# TEC_Laser.net
KiCad netlist of a schematic drawn in Altium Designer
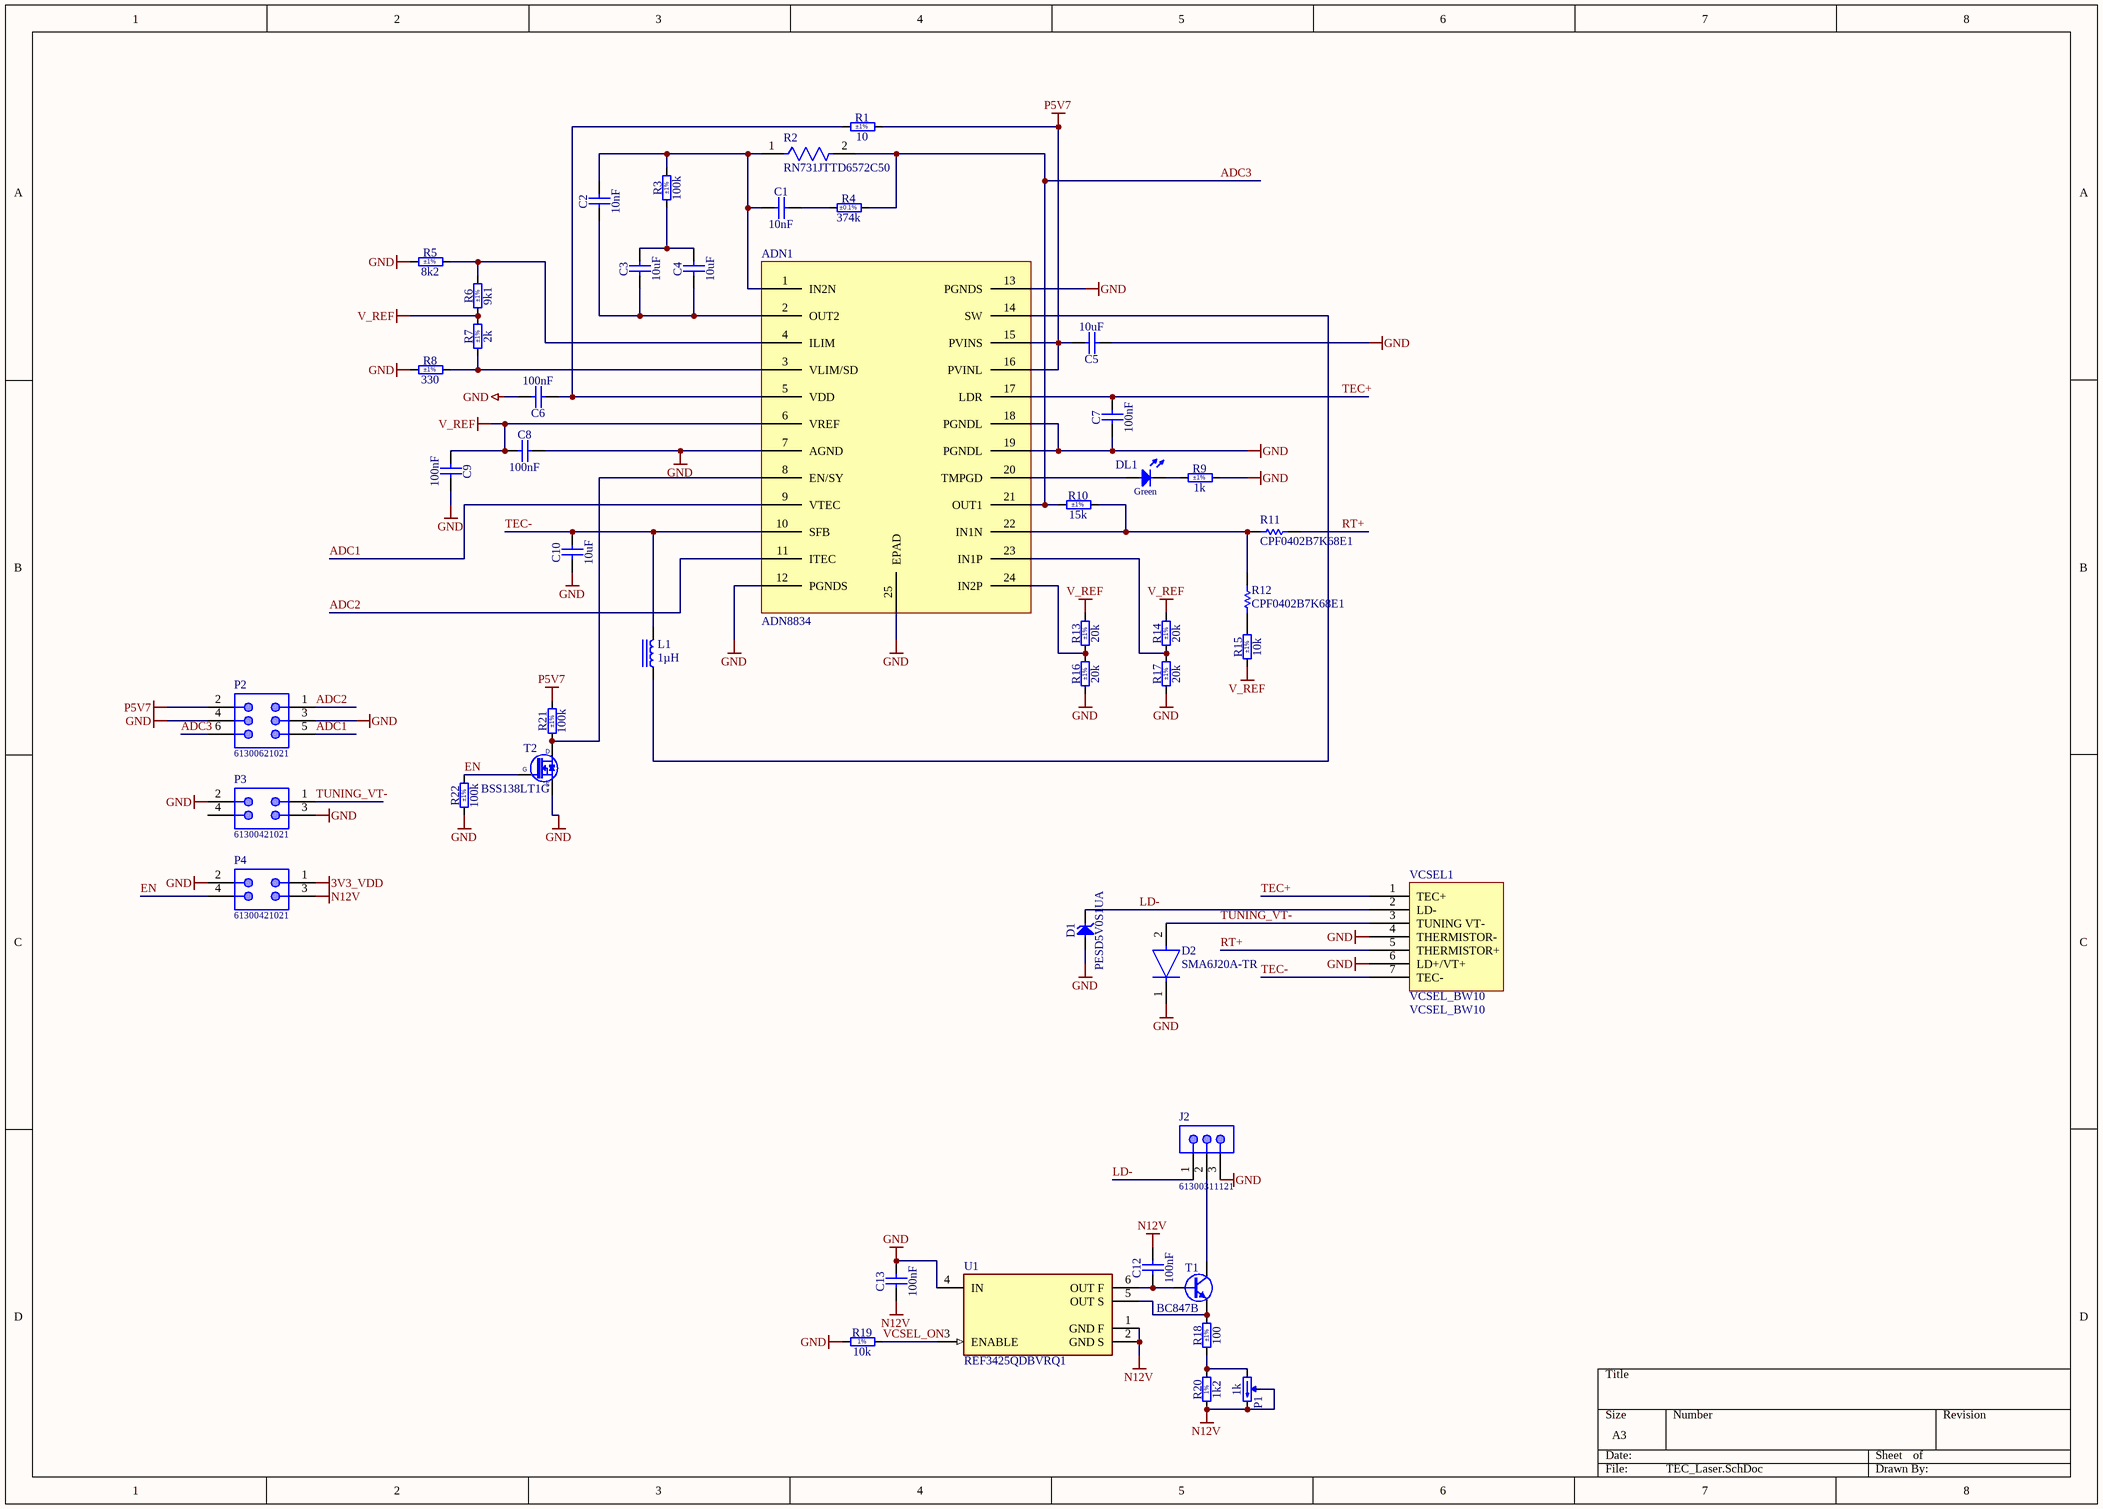
[diagram p0: TEC_Laser.SchDoc]

(export (version "E")
  (design (tool "Eeschema 10.0.6"))
  (components
    (comp (ref "ADN1")
      (value "ADN8834")
      (footprint "SMSC QFN-24 4x4MM")
      (description "TEC")
      (libsource (lib "VCSEL_Driver_Lib") (part "ADN8834"))
    )
    (comp (ref "C1")
      (value "10nF")
      (footprint "CAPC1005X55N")
      (description "Non-polarised capacitor")
      (fields
        (field (name "PART NUMBER") "CC0402_10NF_16V_10%_X7R")
        (field (name "VOLTAGE") "16V")
        (field (name "AUTHOR") "CERN DEM JLC")
      )
      (libsource (lib "Capacitors") (part "Capacitor - non polarized"))
    )
    (comp (ref "C2")
      (value "10nF")
      (footprint "CAPC1005X55N")
      (description "Non-polarised capacitor")
      (fields
        (field (name "PART NUMBER") "CC0402_10NF_16V_10%_X7R")
        (field (name "VOLTAGE") "16V")
        (field (name "AUTHOR") "CERN DEM JLC")
      )
      (libsource (lib "Capacitors") (part "Capacitor - non polarized"))
    )
    (comp (ref "C3")
      (value "10uF")
      (footprint "CAPC1608X80N")
      (description "Non-polarised capacitor")
      (fields
        (field (name "PART NUMBER") "CC0603_10UF_16V_20%_X5R")
        (field (name "VOLTAGE") "16V")
        (field (name "AUTHOR") "CERN DEM MR")
      )
      (libsource (lib "Capacitors") (part "Capacitor - non polarized"))
    )
    (comp (ref "C4")
      (value "10uF")
      (footprint "CAPC1608X80N")
      (description "Non-polarised capacitor")
      (fields
        (field (name "PART NUMBER") "CC0603_10UF_16V_20%_X5R")
        (field (name "VOLTAGE") "16V")
        (field (name "AUTHOR") "CERN DEM MR")
      )
      (libsource (lib "Capacitors") (part "Capacitor - non polarized"))
    )
    (comp (ref "C5")
      (value "10uF")
      (footprint "CAPC1005X70N")
      (description "Non-polarised capacitor")
      (fields
        (field (name "PART NUMBER") "CC0402_10UF_6.3V_20%_X5R")
        (field (name "VOLTAGE") "6.3V")
        (field (name "AUTHOR") "CERN DEM JLC")
      )
      (libsource (lib "Capacitors") (part "Capacitor - non polarized"))
    )
    (comp (ref "C6")
      (value "100nF")
      (footprint "CAPC1005X55N")
      (description "Non-polarised capacitor")
      (fields
        (field (name "PART NUMBER") "CC0402_100NF_16V_10%_X7R")
        (field (name "VOLTAGE") "16V")
        (field (name "AUTHOR") "CERN DEM JLC")
      )
      (libsource (lib "Capacitors") (part "Capacitor - non polarized"))
    )
    (comp (ref "C7")
      (value "100nF")
      (footprint "CAPC1005X55N")
      (description "Non-polarised capacitor")
      (fields
        (field (name "PART NUMBER") "CC0402_100NF_16V_10%_X7R")
        (field (name "VOLTAGE") "16V")
        (field (name "AUTHOR") "CERN DEM JLC")
      )
      (libsource (lib "Capacitors") (part "Capacitor - non polarized"))
    )
    (comp (ref "C8")
      (value "100nF")
      (footprint "CAPC1005X55N")
      (description "Non-polarised capacitor")
      (fields
        (field (name "PART NUMBER") "CC0402_100NF_16V_10%_X7R")
        (field (name "VOLTAGE") "16V")
        (field (name "AUTHOR") "CERN DEM JLC")
      )
      (libsource (lib "Capacitors") (part "Capacitor - non polarized"))
    )
    (comp (ref "C9")
      (value "100nF")
      (footprint "CAPC1005X55N")
      (description "Non-polarised capacitor")
      (fields
        (field (name "PART NUMBER") "CC0402_100NF_16V_10%_X7R")
        (field (name "VOLTAGE") "16V")
        (field (name "AUTHOR") "CERN DEM JLC")
      )
      (libsource (lib "Capacitors") (part "Capacitor - non polarized"))
    )
    (comp (ref "C10")
      (value "10uF")
      (footprint "CAPC1005X70N")
      (description "Non-polarised capacitor")
      (fields
        (field (name "PART NUMBER") "CC0402_10UF_6.3V_20%_X5R")
        (field (name "VOLTAGE") "6.3V")
        (field (name "AUTHOR") "CERN DEM JLC")
      )
      (libsource (lib "Capacitors") (part "Capacitor - non polarized"))
    )
    (comp (ref "C12")
      (value "100nF")
      (footprint "CAPC1005X55N")
      (description "Non-polarised capacitor")
      (fields
        (field (name "PART NUMBER") "CC0402_100NF_16V_10%_X7R")
        (field (name "VOLTAGE") "16V")
        (field (name "AUTHOR") "CERN DEM JLC")
      )
      (libsource (lib "Capacitors") (part "Capacitor - non polarized"))
    )
    (comp (ref "C13")
      (value "100nF")
      (footprint "CAPC1005X55N")
      (description "Non-polarised capacitor")
      (fields
        (field (name "PART NUMBER") "CC0402_100NF_16V_10%_X7R")
        (field (name "VOLTAGE") "16V")
        (field (name "AUTHOR") "CERN DEM JLC")
      )
      (libsource (lib "Capacitors") (part "Capacitor - non polarized"))
    )
    (comp (ref "D1")
      (value "PESD5V0S1UA")
      (footprint "SOD2512X110N")
      (description "Transient Voltage Suppressor Diode (Uni-Directional)")
      (fields
        (field (name "VOLTAGE") "5V")
        (field (name "POWER") "890W")
        (field (name "AUTHOR") "CERN DEM JLC")
      )
      (libsource (lib "ICs And Semiconductors") (part "Diode TVS Uni-Directional"))
    )
    (comp (ref "D2")
      (value "SMA6J20A-TR")
      (footprint "FP-SMA-MFG")
      (description "TVS DIODE 20V 36.8V SMA")
      (libsource (lib "Altium Content Vault") (part "d7152d700b627762746794eb795d46e"))
    )
    (comp (ref "DL1")
      (value "Green")
      (footprint "LED_OSRAM_LGL29K")
      (description "LED Green 1C 2A")
      (fields
        (field (name "PART NUMBER") "LED_OSRAM_LG L29K-G2J1-24-Z")
        (field (name "MANUFACTURER") "OSRAM")
        (field (name "AUTHOR") "CERN DEM JLC")
      )
      (libsource (lib "ICs And Semiconductors") (part "LED Green 1C 2A"))
    )
    (comp (ref "J2")
      (value "61300311121")
      (footprint "61300311121")
      (description "WR-PHD Pin Header, THT, pitch 2.54mm, Single Row, Vertical, 3pin")
      (fields (field (name "PUBLISHER") "Wurth Elektronik"))
      (libsource (lib "ALTIUM-WR-PHD_PIN_HEADER_SOCKET_HEADER-rev19a") (part "61300311121"))
    )
    (comp (ref "L1")
      (value "1µH")
      (footprint "IND 0806_2016")
      (description "FIXED IND 1UH 1.7A 107MOHM SMD")
      (fields
        (field (name "PART NUMBER") "SDED20161T-1R0MS")
        (field (name "MANUFACTURER") "Delta Electronics/Cyntec")
      )
      (libsource (lib "Celestial Altium Library - altium_library") (part "Inductor"))
    )
    (comp (ref "P1")
      (value "1k")
      (footprint "TRIM_VISHAY_T63XB")
      (description "Trimming Potentiometer")
      (fields
        (field (name "PART NUMBER") "TRIM_14T_1K_VISHAY_T63XB102KT20")
        (field (name "POWER") "0.25W")
        (field (name "AUTHOR") "CERN DEM JLC")
      )
      (libsource (lib "Resistors") (part "Trimming Potentiometer"))
    )
    (comp (ref "P2")
      (value "61300621021")
      (footprint "61300621021")
      (description "WR-PHD Pin Header, THT, pitch 2.54mm, Dual Row, Angled, 6p")
      (fields (field (name "MANUFACTURER") "Wurth Elektronik"))
      (libsource (lib "Altium_WR-PHD (rev20a)") (part "61300621021"))
    )
    (comp (ref "P3")
      (value "61300421021")
      (footprint "61300421021")
      (description "WR-PHD Pin Header, THT, pitch 2.54mm, Dual Row, Angled, 4p")
      (fields (field (name "MANUFACTURER") "Wurth Elektronik"))
      (libsource (lib "Altium_WR-PHD (rev20a)") (part "61300421021"))
    )
    (comp (ref "P4")
      (value "61300421021")
      (footprint "61300421021")
      (description "WR-PHD Pin Header, THT, pitch 2.54mm, Dual Row, Angled, 4p")
      (fields (field (name "MANUFACTURER") "Wurth Elektronik"))
      (libsource (lib "Altium_WR-PHD (rev20a)") (part "61300421021"))
    )
    (comp (ref "R1")
      (value "10")
      (footprint "RESC1005X40N")
      (description "Resistor - 1%")
      (fields
        (field (name "TOLERANCE") "±1%")
        (field (name "PART NUMBER") "R0402_10R_1%_0.0625W_200PPM")
        (field (name "POWER") "0.0625W")
        (field (name "AUTHOR") "CERN DEM JLC")
      )
      (libsource (lib "Resistors") (part "Resistor - 1%"))
    )
    (comp (ref "R2")
      (value "RN731JTTD6572C50")
      (footprint "FP-RN731J-IPC_B")
      (description "65.7kΩ ±0.25% 0.063W, 1/16W Chip Resistor 0603 (1608 Metric) Moisture Resistant Thin Film")
      (fields (field (name "TOLERANCE") "0.25%"))
      (libsource (lib "Altium Content Vault") (part "1029c3af85768c4190bb7ad29bc67b5"))
    )
    (comp (ref "R3")
      (value "100k")
      (footprint "RESC1005X40N")
      (description "Resistor - 1%")
      (fields
        (field (name "TOLERANCE") "±1%")
        (field (name "PART NUMBER") "R0402_100K_1%_0.0625W_100PPM")
        (field (name "POWER") "0.0625W")
        (field (name "AUTHOR") "CERN DEM JLC")
      )
      (libsource (lib "Resistors") (part "Resistor - 1%"))
    )
    (comp (ref "R4")
      (value "374k")
      (footprint "RESC1608X55N")
      (description "Resistor - 0.1%")
      (fields
        (field (name "TOLERANCE") "±0.1%")
        (field (name "PART NUMBER") "R0603_374K_0.1%_0.063W_25PPM")
        (field (name "POWER") "0.063W")
        (field (name "AUTHOR") "CERN DEM JLC")
      )
      (libsource (lib "Resistors") (part "Resistor - 0.1%"))
    )
    (comp (ref "R5")
      (value "8k2")
      (footprint "RESC1005X40N")
      (description "Resistor - 1%")
      (fields
        (field (name "TOLERANCE") "±1%")
        (field (name "PART NUMBER") "R0402_8K2_1%_0.0625W_100PPM")
        (field (name "POWER") "0.0625W")
        (field (name "AUTHOR") "CERN DEM JLC")
      )
      (libsource (lib "Resistors") (part "Resistor - 1%"))
    )
    (comp (ref "R6")
      (value "9k1")
      (footprint "RESC1005X40N")
      (description "Resistor - 1%")
      (fields
        (field (name "TOLERANCE") "±1%")
        (field (name "PART NUMBER") "R0402_9K1_1%_0.0625W_100PPM")
        (field (name "POWER") "0.0625W")
        (field (name "AUTHOR") "CERN DEM JLC")
      )
      (libsource (lib "Resistors") (part "Resistor - 1%"))
    )
    (comp (ref "R7")
      (value "2k")
      (footprint "RESC1005X40N")
      (description "Resistor - 1%")
      (fields
        (field (name "TOLERANCE") "±1%")
        (field (name "PART NUMBER") "R0402_2K_1%_0.0625W_100PPM")
        (field (name "POWER") "0.0625W")
        (field (name "AUTHOR") "CERN DEM JLC")
      )
      (libsource (lib "Resistors") (part "Resistor - 1%"))
    )
    (comp (ref "R8")
      (value "330")
      (footprint "RESC1005X40N")
      (description "Resistor - 1%")
      (fields
        (field (name "TOLERANCE") "±1%")
        (field (name "PART NUMBER") "R0402_330R_1%_0.0625W_100PPM")
        (field (name "POWER") "0.0625W")
        (field (name "AUTHOR") "CERN DEM JLC")
      )
      (libsource (lib "Resistors") (part "Resistor - 1%"))
    )
    (comp (ref "R9")
      (value "1k")
      (footprint "RESC1005X40N")
      (description "Resistor - 1%")
      (fields
        (field (name "TOLERANCE") "±1%")
        (field (name "PART NUMBER") "R0402_1K_1%_0.0625W_100PPM")
        (field (name "POWER") "0.0625W")
        (field (name "AUTHOR") "CERN DEM JLC")
      )
      (libsource (lib "Resistors") (part "Resistor - 1%"))
    )
    (comp (ref "R10")
      (value "15k")
      (footprint "RESC1005X40N")
      (description "Resistor - 1%")
      (fields
        (field (name "TOLERANCE") "±1%")
        (field (name "PART NUMBER") "R0402_15K_1%_0.0625W_100PPM")
        (field (name "POWER") "0.0625W")
        (field (name "AUTHOR") "CERN DEM JMW")
      )
      (libsource (lib "Resistors") (part "Resistor - 1%"))
    )
    (comp (ref "R11")
      (value "CPF0402B7K68E1")
      (footprint "RESC1005X35X20NL05T10")
      (fields (field (name "MANUFACTURER") "TE Connectivity / AMP"))
      (libsource (lib "Altium Content Vault") (part "RES"))
    )
    (comp (ref "R12")
      (value "CPF0402B7K68E1")
      (footprint "RESC1005X35X20NL05T10")
      (fields (field (name "MANUFACTURER") "TE Connectivity / AMP"))
      (libsource (lib "Altium Content Vault") (part "RES"))
    )
    (comp (ref "R13")
      (value "20k")
      (footprint "RESC1005X40N")
      (description "Resistor - 1%")
      (fields
        (field (name "TOLERANCE") "±1%")
        (field (name "PART NUMBER") "R0402_20K_1%_0.0625W_100PPM")
        (field (name "POWER") "0.0625W")
        (field (name "AUTHOR") "CERN DEM JLC")
      )
      (libsource (lib "Resistors") (part "Resistor - 1%"))
    )
    (comp (ref "R14")
      (value "20k")
      (footprint "RESC1005X40N")
      (description "Resistor - 1%")
      (fields
        (field (name "TOLERANCE") "±1%")
        (field (name "PART NUMBER") "R0402_20K_1%_0.0625W_100PPM")
        (field (name "POWER") "0.0625W")
        (field (name "AUTHOR") "CERN DEM JLC")
      )
      (libsource (lib "Resistors") (part "Resistor - 1%"))
    )
    (comp (ref "R15")
      (value "10k")
      (footprint "RESC1005X40N")
      (description "Resistor - 1%")
      (fields
        (field (name "TOLERANCE") "±1%")
        (field (name "PART NUMBER") "R0402_10K_1%_0.0625W_100PPM")
        (field (name "POWER") "0.0625W")
        (field (name "AUTHOR") "CERN DEM JLC")
      )
      (libsource (lib "Resistors") (part "Resistor - 1%"))
    )
    (comp (ref "R16")
      (value "20k")
      (footprint "RESC1005X40N")
      (description "Resistor - 1%")
      (fields
        (field (name "TOLERANCE") "±1%")
        (field (name "PART NUMBER") "R0402_20K_1%_0.0625W_100PPM")
        (field (name "POWER") "0.0625W")
        (field (name "AUTHOR") "CERN DEM JLC")
      )
      (libsource (lib "Resistors") (part "Resistor - 1%"))
    )
    (comp (ref "R17")
      (value "20k")
      (footprint "RESC1005X40N")
      (description "Resistor - 1%")
      (fields
        (field (name "TOLERANCE") "±1%")
        (field (name "PART NUMBER") "R0402_20K_1%_0.0625W_100PPM")
        (field (name "POWER") "0.0625W")
        (field (name "AUTHOR") "CERN DEM JLC")
      )
      (libsource (lib "Resistors") (part "Resistor - 1%"))
    )
    (comp (ref "R18")
      (value "100")
      (footprint "RESC1005X40N")
      (description "Resistor - 1%")
      (fields
        (field (name "TOLERANCE") "±1%")
        (field (name "PART NUMBER") "R0402_100R_1%_0.0625W_100PPM")
        (field (name "POWER") "0.0625W")
        (field (name "AUTHOR") "CERN DEM JLC")
      )
      (libsource (lib "Resistors") (part "Resistor - 1%"))
    )
    (comp (ref "R19")
      (value "10k")
      (footprint "RESC1005X40N")
      (description "Resistor - 1%")
      (fields
        (field (name "PART NUMBER") "R0402_10K_1%_0.0625W_100PPM")
        (field (name "POWER") "0.0625W")
        (field (name "AUTHOR") "CERN DEM JLC")
      )
      (libsource (lib "Resistors") (part "Resistor - 1%"))
    )
    (comp (ref "R20")
      (value "1k2")
      (footprint "RESC1005X40N")
      (description "Resistor - 1%")
      (fields
        (field (name "PART NUMBER") "R0402_1K2_1%_0.0625W_100PPM")
        (field (name "POWER") "0.0625W")
        (field (name "AUTHOR") "CERN DEM JLC")
      )
      (libsource (lib "Resistors") (part "Resistor - 1%"))
    )
    (comp (ref "R21")
      (value "100k")
      (footprint "RESC1005X40N")
      (description "Resistor - 1%")
      (fields
        (field (name "TOLERANCE") "±1%")
        (field (name "PART NUMBER") "R0402_100K_1%_0.0625W_100PPM")
        (field (name "POWER") "0.0625W")
        (field (name "AUTHOR") "CERN DEM JLC")
      )
      (libsource (lib "Resistors") (part "Resistor - 1%"))
    )
    (comp (ref "R22")
      (value "100k")
      (footprint "RESC1005X40N")
      (description "Resistor - 1%")
      (fields
        (field (name "TOLERANCE") "±1%")
        (field (name "PART NUMBER") "R0402_100K_1%_0.0625W_100PPM")
        (field (name "POWER") "0.0625W")
        (field (name "AUTHOR") "CERN DEM JLC")
      )
      (libsource (lib "Resistors") (part "Resistor - 1%"))
    )
    (comp (ref "T1")
      (value "BC847B")
      (footprint "SOT95P230X110-3N")
      (description "NPN Transistor")
      (fields (field (name "MANUFACTURER") "NXP SEMICONDUCTORS") (field (name "AUTHOR") "CERN DEM JLC"))
      (libsource (lib "ICs And Semiconductors") (part "NPN B1 E2 C3"))
    )
    (comp (ref "T2")
      (value "BSS138LT1G")
      (footprint "SOT95P240X110-3N")
      (description "N-CHANNEL MOSFET WITH DIODE")
      (fields (field (name "MANUFACTURER") "ON SEMICONDUCTOR") (field (name "AUTHOR") "CERN DEM JLC"))
      (libsource (lib "ICs And Semiconductors") (part "N-MOSFET-D 1G 2S 3D"))
    )
    (comp (ref "U1")
      (value "REF3425QDBVRQ1")
      (footprint "FP-DBV0006A-MFG")
      (description "IC VREF SERIES 0.05% SOT23-6")
      (fields
        (field (name "OCTOPART") "https://octopart.com/ref3433qdbvrq1-texas+instruments-95842010")
        (field (name "MANUFACTURER") "Texas Instruments")
      )
      (libsource (lib "Altium Content Vault") (part "852d3c1243c2caefb114a4c8e829102"))
    )
    (comp (ref "VCSEL1")
      (value "VCSEL_BW10")
      (footprint "VCSEL_BW10")
      (libsource (lib "MG_lib") (part "VCSLE_BW10"))
    )
  )
  (nets
    (net (code "1") (name "/ADC1") (class "Default")
      (node (ref "ADN1") (pin "9") (pinfunction "VTEC_9") (pintype "passive"))
      (node (ref "P2") (pin "5") (pinfunction "5_5") (pintype "passive"))
    )
    (net (code "2") (name "/ADC2") (class "Default")
      (node (ref "ADN1") (pin "11") (pinfunction "ITEC_11") (pintype "passive"))
      (node (ref "P2") (pin "1") (pinfunction "1_1") (pintype "passive"))
    )
    (net (code "3") (name "/ADC3") (class "Default")
      (node (ref "ADN1") (pin "21") (pinfunction "OUT1_21") (pintype "passive"))
      (node (ref "P2") (pin "6") (pinfunction "6_6") (pintype "passive"))
      (node (ref "R10") (pin "1") (pinfunction "1_1") (pintype "passive"))
      (node (ref "R2") (pin "2") (pinfunction "2_2") (pintype "passive"))
      (node (ref "R4") (pin "2") (pinfunction "2_2") (pintype "passive"))
    )
    (net (code "4") (name "/EN") (class "Default")
      (node (ref "P4") (pin "4") (pinfunction "4_4") (pintype "passive"))
      (node (ref "R22") (pin "2") (pinfunction "2_2") (pintype "passive"))
      (node (ref "T2") (pin "1") (pinfunction "G_1") (pintype "passive"))
    )
    (net (code "5") (name "/LD-") (class "Default")
      (node (ref "D1") (pin "1") (pinfunction "C_1") (pintype "passive"))
      (node (ref "J2") (pin "1") (pinfunction "1_1") (pintype "passive"))
      (node (ref "VCSEL1") (pin "2") (pinfunction "LD-_2") (pintype "passive"))
    )
    (net (code "6") (name "/RT+") (class "Default")
      (node (ref "R11") (pin "2") (pinfunction "2_2") (pintype "passive"))
      (node (ref "VCSEL1") (pin "5") (pinfunction "THERMISTOR+_5") (pintype "passive"))
    )
    (net (code "7") (name "/TEC+") (class "Default")
      (node (ref "ADN1") (pin "17") (pinfunction "LDR_17") (pintype "passive"))
      (node (ref "C7") (pin "2") (pinfunction "2_2") (pintype "passive"))
      (node (ref "VCSEL1") (pin "1") (pinfunction "TEC+_1") (pintype "passive"))
    )
    (net (code "8") (name "/TEC-") (class "Default")
      (node (ref "ADN1") (pin "10") (pinfunction "SFB_10") (pintype "passive"))
      (node (ref "C10") (pin "2") (pinfunction "2_2") (pintype "passive"))
      (node (ref "L1") (pin "2") (pinfunction "2_2") (pintype "passive"))
      (node (ref "VCSEL1") (pin "7") (pinfunction "TEC-_7") (pintype "passive"))
    )
    (net (code "9") (name "/TUNING_VT-") (class "Default")
      (node (ref "D2") (pin "2") (pinfunction "A_2") (pintype "passive"))
      (node (ref "P3") (pin "1") (pinfunction "1_1") (pintype "passive"))
      (node (ref "VCSEL1") (pin "3") (pinfunction "TUNING_VT-_3") (pintype "passive"))
    )
    (net (code "10") (name "/VCSEL_ON") (class "Default")
      (node (ref "R19") (pin "2") (pinfunction "2_2") (pintype "passive"))
      (node (ref "U1") (pin "3") (pinfunction "ENABLE_3") (pintype "input"))
    )
    (net (code "11") (name "3V3_VDD") (class "Default")
      (node (ref "P4") (pin "1") (pinfunction "1_1") (pintype "passive"))
    )
    (net (code "12") (name "GND") (class "Default")
      (node (ref "ADN1") (pin "12") (pinfunction "PGNDS_12") (pintype "passive"))
      (node (ref "ADN1") (pin "13") (pinfunction "PGNDS_13") (pintype "passive"))
      (node (ref "ADN1") (pin "18") (pinfunction "PGNDL_18") (pintype "passive"))
      (node (ref "ADN1") (pin "19") (pinfunction "PGNDL_19") (pintype "passive"))
      (node (ref "ADN1") (pin "25") (pinfunction "EPAD_25") (pintype "passive"))
      (node (ref "ADN1") (pin "7") (pinfunction "AGND_7") (pintype "passive"))
      (node (ref "C10") (pin "1") (pinfunction "1_1") (pintype "passive"))
      (node (ref "C13") (pin "2") (pinfunction "2_2") (pintype "passive"))
      (node (ref "C5") (pin "1") (pinfunction "1_1") (pintype "passive"))
      (node (ref "C6") (pin "2") (pinfunction "2_2") (pintype "passive"))
      (node (ref "C7") (pin "1") (pinfunction "1_1") (pintype "passive"))
      (node (ref "C8") (pin "2") (pinfunction "2_2") (pintype "passive"))
      (node (ref "C9") (pin "2") (pinfunction "2_2") (pintype "passive"))
      (node (ref "D1") (pin "2") (pinfunction "A_2") (pintype "passive"))
      (node (ref "D2") (pin "1") (pinfunction "C_1") (pintype "passive"))
      (node (ref "J2") (pin "3") (pinfunction "3_3") (pintype "passive"))
      (node (ref "P2") (pin "3") (pinfunction "3_3") (pintype "passive"))
      (node (ref "P2") (pin "4") (pinfunction "4_4") (pintype "passive"))
      (node (ref "P3") (pin "2") (pinfunction "2_2") (pintype "passive"))
      (node (ref "P3") (pin "3") (pinfunction "3_3") (pintype "passive"))
      (node (ref "P4") (pin "2") (pinfunction "2_2") (pintype "passive"))
      (node (ref "R16") (pin "1") (pinfunction "1_1") (pintype "passive"))
      (node (ref "R17") (pin "1") (pinfunction "1_1") (pintype "passive"))
      (node (ref "R19") (pin "1") (pinfunction "1_1") (pintype "passive"))
      (node (ref "R22") (pin "1") (pinfunction "1_1") (pintype "passive"))
      (node (ref "R5") (pin "1") (pinfunction "1_1") (pintype "passive"))
      (node (ref "R8") (pin "1") (pinfunction "1_1") (pintype "passive"))
      (node (ref "R9") (pin "2") (pinfunction "2_2") (pintype "passive"))
      (node (ref "T2") (pin "2") (pinfunction "S_2") (pintype "passive"))
      (node (ref "U1") (pin "4") (pinfunction "IN_4") (pintype "power_in"))
      (node (ref "VCSEL1") (pin "4") (pinfunction "THERMISTOR-_4") (pintype "passive"))
      (node (ref "VCSEL1") (pin "6") (pinfunction "LD+/VT+_6") (pintype "passive"))
    )
    (net (code "13") (name "N12V") (class "Default")
      (node (ref "C12") (pin "2") (pinfunction "2_2") (pintype "passive"))
      (node (ref "C13") (pin "1") (pinfunction "1_1") (pintype "passive"))
      (node (ref "P1") (pin "2") (pinfunction "W_2") (pintype "passive"))
      (node (ref "P1") (pin "3") (pinfunction "CW_3") (pintype "passive"))
      (node (ref "P4") (pin "3") (pinfunction "3_3") (pintype "passive"))
      (node (ref "R20") (pin "1") (pinfunction "1_1") (pintype "passive"))
      (node (ref "U1") (pin "1") (pinfunction "GND_F_1") (pintype "power_in"))
      (node (ref "U1") (pin "2") (pinfunction "GND_S_2") (pintype "power_in"))
    )
    (net (code "14") (name "Net-(ADN1-EN{slash}SY)") (class "Default")
      (node (ref "ADN1") (pin "8") (pinfunction "EN/SY_8") (pintype "passive"))
      (node (ref "R21") (pin "1") (pinfunction "1_1") (pintype "passive"))
      (node (ref "T2") (pin "3") (pinfunction "D_3") (pintype "passive"))
    )
    (net (code "15") (name "Net-(ADN1-ILIM)") (class "Default")
      (node (ref "ADN1") (pin "4") (pinfunction "ILIM_4") (pintype "passive"))
      (node (ref "R5") (pin "2") (pinfunction "2_2") (pintype "passive"))
      (node (ref "R6") (pin "2") (pinfunction "2_2") (pintype "passive"))
    )
    (net (code "16") (name "Net-(ADN1-IN1N)") (class "Default")
      (node (ref "ADN1") (pin "22") (pinfunction "IN1N_22") (pintype "passive"))
      (node (ref "R10") (pin "2") (pinfunction "2_2") (pintype "passive"))
      (node (ref "R11") (pin "1") (pinfunction "1_1") (pintype "passive"))
      (node (ref "R12") (pin "2") (pinfunction "2_2") (pintype "passive"))
    )
    (net (code "17") (name "Net-(ADN1-IN1P)") (class "Default")
      (node (ref "ADN1") (pin "23") (pinfunction "IN1P_23") (pintype "passive"))
      (node (ref "R14") (pin "1") (pinfunction "1_1") (pintype "passive"))
      (node (ref "R17") (pin "2") (pinfunction "2_2") (pintype "passive"))
    )
    (net (code "18") (name "Net-(ADN1-IN2N)") (class "Default")
      (node (ref "ADN1") (pin "1") (pinfunction "IN2N_1") (pintype "passive"))
      (node (ref "C1") (pin "1") (pinfunction "1_1") (pintype "passive"))
      (node (ref "C2") (pin "2") (pinfunction "2_2") (pintype "passive"))
      (node (ref "R2") (pin "1") (pinfunction "1_1") (pintype "passive"))
      (node (ref "R3") (pin "2") (pinfunction "2_2") (pintype "passive"))
    )
    (net (code "19") (name "Net-(ADN1-IN2P)") (class "Default")
      (node (ref "ADN1") (pin "24") (pinfunction "IN2P_24") (pintype "passive"))
      (node (ref "R13") (pin "1") (pinfunction "1_1") (pintype "passive"))
      (node (ref "R16") (pin "2") (pinfunction "2_2") (pintype "passive"))
    )
    (net (code "20") (name "Net-(ADN1-OUT2)") (class "Default")
      (node (ref "ADN1") (pin "2") (pinfunction "OUT2_2") (pintype "passive"))
      (node (ref "C2") (pin "1") (pinfunction "1_1") (pintype "passive"))
      (node (ref "C3") (pin "1") (pinfunction "1_1") (pintype "passive"))
      (node (ref "C4") (pin "1") (pinfunction "1_1") (pintype "passive"))
    )
    (net (code "21") (name "Net-(ADN1-SW)") (class "Default")
      (node (ref "ADN1") (pin "14") (pinfunction "SW_14") (pintype "passive"))
      (node (ref "L1") (pin "1") (pinfunction "1_1") (pintype "passive"))
    )
    (net (code "22") (name "Net-(ADN1-TMPGD)") (class "Default")
      (node (ref "ADN1") (pin "20") (pinfunction "TMPGD_20") (pintype "passive"))
      (node (ref "DL1") (pin "2") (pinfunction "A_2") (pintype "passive"))
    )
    (net (code "23") (name "Net-(ADN1-VDD)") (class "Default")
      (node (ref "ADN1") (pin "5") (pinfunction "VDD_5") (pintype "passive"))
      (node (ref "C6") (pin "1") (pinfunction "1_1") (pintype "passive"))
      (node (ref "R1") (pin "1") (pinfunction "1_1") (pintype "passive"))
    )
    (net (code "24") (name "Net-(ADN1-VLIM{slash}SD)") (class "Default")
      (node (ref "ADN1") (pin "3") (pinfunction "VLIM/SD_3") (pintype "passive"))
      (node (ref "R7") (pin "1") (pinfunction "1_1") (pintype "passive"))
      (node (ref "R8") (pin "2") (pinfunction "2_2") (pintype "passive"))
    )
    (net (code "25") (name "Net-(C1-Pad2)") (class "Default")
      (node (ref "C1") (pin "2") (pinfunction "2_2") (pintype "passive"))
      (node (ref "R4") (pin "1") (pinfunction "1_1") (pintype "passive"))
    )
    (net (code "26") (name "Net-(C3-Pad2)") (class "Default")
      (node (ref "C3") (pin "2") (pinfunction "2_2") (pintype "passive"))
      (node (ref "C4") (pin "2") (pinfunction "2_2") (pintype "passive"))
      (node (ref "R3") (pin "1") (pinfunction "1_1") (pintype "passive"))
    )
    (net (code "27") (name "Net-(DL1-C)") (class "Default")
      (node (ref "DL1") (pin "1") (pinfunction "C_1") (pintype "passive"))
      (node (ref "R9") (pin "1") (pinfunction "1_1") (pintype "passive"))
    )
    (net (code "28") (name "Net-(P1-CCW)") (class "Default")
      (node (ref "P1") (pin "1") (pinfunction "CCW_1") (pintype "passive"))
      (node (ref "R18") (pin "1") (pinfunction "1_1") (pintype "passive"))
      (node (ref "R20") (pin "2") (pinfunction "2_2") (pintype "passive"))
    )
    (net (code "29") (name "Net-(R12-Pad1)") (class "Default")
      (node (ref "R12") (pin "1") (pinfunction "1_1") (pintype "passive"))
      (node (ref "R15") (pin "2") (pinfunction "2_2") (pintype "passive"))
    )
    (net (code "30") (name "Net-(T1-B)") (class "Default")
      (node (ref "C12") (pin "1") (pinfunction "1_1") (pintype "passive"))
      (node (ref "T1") (pin "1") (pinfunction "B_1") (pintype "passive"))
      (node (ref "U1") (pin "6") (pinfunction "OUT_F_6") (pintype "power_in"))
    )
    (net (code "31") (name "Net-(T1-C)") (class "Default")
      (node (ref "J2") (pin "2") (pinfunction "2_2") (pintype "passive"))
      (node (ref "T1") (pin "3") (pinfunction "C_3") (pintype "passive"))
    )
    (net (code "32") (name "Net-(T1-E)") (class "Default")
      (node (ref "R18") (pin "2") (pinfunction "2_2") (pintype "passive"))
      (node (ref "T1") (pin "2") (pinfunction "E_2") (pintype "passive"))
      (node (ref "U1") (pin "5") (pinfunction "OUT_S_5") (pintype "power_in"))
    )
    (net (code "33") (name "P5V7") (class "Default")
      (node (ref "ADN1") (pin "15") (pinfunction "PVINS_15") (pintype "passive"))
      (node (ref "ADN1") (pin "16") (pinfunction "PVINL_16") (pintype "passive"))
      (node (ref "C5") (pin "2") (pinfunction "2_2") (pintype "passive"))
      (node (ref "P2") (pin "2") (pinfunction "2_2") (pintype "passive"))
      (node (ref "R1") (pin "2") (pinfunction "2_2") (pintype "passive"))
      (node (ref "R21") (pin "2") (pinfunction "2_2") (pintype "passive"))
    )
    (net (code "34") (name "V_REF") (class "Default")
      (node (ref "ADN1") (pin "6") (pinfunction "VREF_6") (pintype "passive"))
      (node (ref "C8") (pin "1") (pinfunction "1_1") (pintype "passive"))
      (node (ref "C9") (pin "1") (pinfunction "1_1") (pintype "passive"))
      (node (ref "R13") (pin "2") (pinfunction "2_2") (pintype "passive"))
      (node (ref "R14") (pin "2") (pinfunction "2_2") (pintype "passive"))
      (node (ref "R15") (pin "1") (pinfunction "1_1") (pintype "passive"))
      (node (ref "R6") (pin "1") (pinfunction "1_1") (pintype "passive"))
      (node (ref "R7") (pin "2") (pinfunction "2_2") (pintype "passive"))
    )
    (net (code "35") (name "unconnected-(P3-Pad4)") (class "Default")
      (node (ref "P3") (pin "4") (pinfunction "4_4") (pintype "passive"))
    )
  )
)
